# Electrode_Array_Hex_PCB.net
KiCad netlist of a schematic drawn in Altium Designer
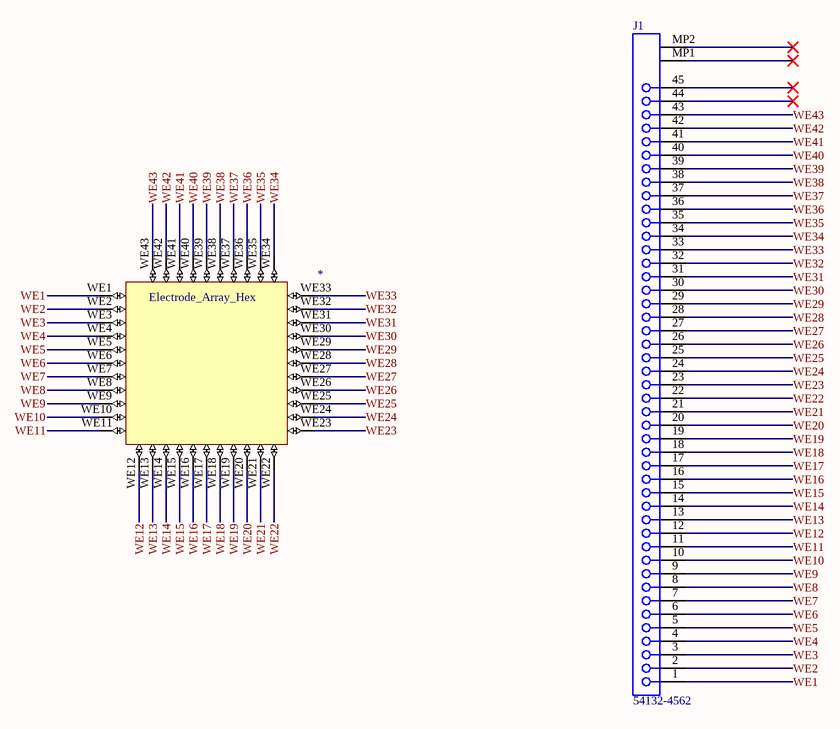
[diagram p0: Electrode_Array_Hex_PCB.SchDoc]

(export (version "E")
  (design (tool "Eeschema 10.0.6"))
  (components
    (comp (ref "*")
      (value "Electrode_Array_Hex")
      (footprint "PCBComponent_1")
      (libsource (lib "Electrode_Array_PCB_Hex") (part "Electrode_Array_Hex"))
    )
    (comp (ref "J1")
      (value "54132-4562")
      (footprint "MOLX-54132-4562")
      (fields (field (name "MANUFACTURER") "Molex"))
      (libsource (lib "Altium Content Vault") (part "MOLX-54132-4562"))
    )
  )
  (nets
    (net (code "1") (name "/WE1") (class "Default")
      (node (ref "*") (pin "WE1") (pintype "bidirectional"))
      (node (ref "J1") (pin "1") (pinfunction "1_1") (pintype "passive"))
    )
    (net (code "2") (name "/WE2") (class "Default")
      (node (ref "*") (pin "WE2") (pintype "bidirectional"))
      (node (ref "J1") (pin "2") (pinfunction "2_2") (pintype "passive"))
    )
    (net (code "3") (name "/WE3") (class "Default")
      (node (ref "*") (pin "WE3") (pintype "bidirectional"))
      (node (ref "J1") (pin "3") (pinfunction "3_3") (pintype "passive"))
    )
    (net (code "4") (name "/WE4") (class "Default")
      (node (ref "*") (pin "WE4") (pintype "bidirectional"))
      (node (ref "J1") (pin "4") (pinfunction "4_4") (pintype "passive"))
    )
    (net (code "5") (name "/WE5") (class "Default")
      (node (ref "*") (pin "WE5") (pintype "bidirectional"))
      (node (ref "J1") (pin "5") (pinfunction "5_5") (pintype "passive"))
    )
    (net (code "6") (name "/WE6") (class "Default")
      (node (ref "*") (pin "WE6") (pintype "bidirectional"))
      (node (ref "J1") (pin "6") (pinfunction "6_6") (pintype "passive"))
    )
    (net (code "7") (name "/WE7") (class "Default")
      (node (ref "*") (pin "WE7") (pintype "bidirectional"))
      (node (ref "J1") (pin "7") (pinfunction "7_7") (pintype "passive"))
    )
    (net (code "8") (name "/WE8") (class "Default")
      (node (ref "*") (pin "WE8") (pintype "bidirectional"))
      (node (ref "J1") (pin "8") (pinfunction "8_8") (pintype "passive"))
    )
    (net (code "9") (name "/WE9") (class "Default")
      (node (ref "*") (pin "WE9") (pintype "bidirectional"))
      (node (ref "J1") (pin "9") (pinfunction "9_9") (pintype "passive"))
    )
    (net (code "10") (name "/WE10") (class "Default")
      (node (ref "*") (pin "WE10") (pintype "bidirectional"))
      (node (ref "J1") (pin "10") (pinfunction "10_10") (pintype "passive"))
    )
    (net (code "11") (name "/WE11") (class "Default")
      (node (ref "*") (pin "WE11") (pintype "bidirectional"))
      (node (ref "J1") (pin "11") (pinfunction "11_11") (pintype "passive"))
    )
    (net (code "12") (name "/WE12") (class "Default")
      (node (ref "*") (pin "WE12") (pintype "bidirectional"))
      (node (ref "J1") (pin "12") (pinfunction "12_12") (pintype "passive"))
    )
    (net (code "13") (name "/WE13") (class "Default")
      (node (ref "*") (pin "WE13") (pintype "bidirectional"))
      (node (ref "J1") (pin "13") (pinfunction "13_13") (pintype "passive"))
    )
    (net (code "14") (name "/WE14") (class "Default")
      (node (ref "*") (pin "WE14") (pintype "bidirectional"))
      (node (ref "J1") (pin "14") (pinfunction "14_14") (pintype "passive"))
    )
    (net (code "15") (name "/WE15") (class "Default")
      (node (ref "*") (pin "WE15") (pintype "bidirectional"))
      (node (ref "J1") (pin "15") (pinfunction "15_15") (pintype "passive"))
    )
    (net (code "16") (name "/WE16") (class "Default")
      (node (ref "*") (pin "WE16") (pintype "bidirectional"))
      (node (ref "J1") (pin "16") (pinfunction "16_16") (pintype "passive"))
    )
    (net (code "17") (name "/WE17") (class "Default")
      (node (ref "*") (pin "WE17") (pintype "bidirectional"))
      (node (ref "J1") (pin "17") (pinfunction "17_17") (pintype "passive"))
    )
    (net (code "18") (name "/WE18") (class "Default")
      (node (ref "*") (pin "WE18") (pintype "bidirectional"))
      (node (ref "J1") (pin "18") (pinfunction "18_18") (pintype "passive"))
    )
    (net (code "19") (name "/WE19") (class "Default")
      (node (ref "*") (pin "WE19") (pintype "bidirectional"))
      (node (ref "J1") (pin "19") (pinfunction "19_19") (pintype "passive"))
    )
    (net (code "20") (name "/WE20") (class "Default")
      (node (ref "*") (pin "WE20") (pintype "bidirectional"))
      (node (ref "J1") (pin "20") (pinfunction "20_20") (pintype "passive"))
    )
    (net (code "21") (name "/WE21") (class "Default")
      (node (ref "*") (pin "WE21") (pintype "bidirectional"))
      (node (ref "J1") (pin "21") (pinfunction "21_21") (pintype "passive"))
    )
    (net (code "22") (name "/WE22") (class "Default")
      (node (ref "*") (pin "WE22") (pintype "bidirectional"))
      (node (ref "J1") (pin "22") (pinfunction "22_22") (pintype "passive"))
    )
    (net (code "23") (name "/WE23") (class "Default")
      (node (ref "*") (pin "WE23") (pintype "bidirectional"))
      (node (ref "J1") (pin "23") (pinfunction "23_23") (pintype "passive"))
    )
    (net (code "24") (name "/WE24") (class "Default")
      (node (ref "*") (pin "WE24") (pintype "bidirectional"))
      (node (ref "J1") (pin "24") (pinfunction "24_24") (pintype "passive"))
    )
    (net (code "25") (name "/WE25") (class "Default")
      (node (ref "*") (pin "WE25") (pintype "bidirectional"))
      (node (ref "J1") (pin "25") (pinfunction "25_25") (pintype "passive"))
    )
    (net (code "26") (name "/WE26") (class "Default")
      (node (ref "*") (pin "WE26") (pintype "bidirectional"))
      (node (ref "J1") (pin "26") (pinfunction "26_26") (pintype "passive"))
    )
    (net (code "27") (name "/WE27") (class "Default")
      (node (ref "*") (pin "WE27") (pintype "bidirectional"))
      (node (ref "J1") (pin "27") (pinfunction "27_27") (pintype "passive"))
    )
    (net (code "28") (name "/WE28") (class "Default")
      (node (ref "*") (pin "WE28") (pintype "bidirectional"))
      (node (ref "J1") (pin "28") (pinfunction "28_28") (pintype "passive"))
    )
    (net (code "29") (name "/WE29") (class "Default")
      (node (ref "*") (pin "WE29") (pintype "bidirectional"))
      (node (ref "J1") (pin "29") (pinfunction "29_29") (pintype "passive"))
    )
    (net (code "30") (name "/WE30") (class "Default")
      (node (ref "*") (pin "WE30") (pintype "bidirectional"))
      (node (ref "J1") (pin "30") (pinfunction "30_30") (pintype "passive"))
    )
    (net (code "31") (name "/WE31") (class "Default")
      (node (ref "*") (pin "WE31") (pintype "bidirectional"))
      (node (ref "J1") (pin "31") (pinfunction "31_31") (pintype "passive"))
    )
    (net (code "32") (name "/WE32") (class "Default")
      (node (ref "*") (pin "WE32") (pintype "bidirectional"))
      (node (ref "J1") (pin "32") (pinfunction "32_32") (pintype "passive"))
    )
    (net (code "33") (name "/WE33") (class "Default")
      (node (ref "*") (pin "WE33") (pintype "bidirectional"))
      (node (ref "J1") (pin "33") (pinfunction "33_33") (pintype "passive"))
    )
    (net (code "34") (name "/WE34") (class "Default")
      (node (ref "*") (pin "WE34") (pintype "bidirectional"))
      (node (ref "J1") (pin "34") (pinfunction "34_34") (pintype "passive"))
    )
    (net (code "35") (name "/WE35") (class "Default")
      (node (ref "*") (pin "WE35") (pintype "bidirectional"))
      (node (ref "J1") (pin "35") (pinfunction "35_35") (pintype "passive"))
    )
    (net (code "36") (name "/WE36") (class "Default")
      (node (ref "*") (pin "WE36") (pintype "bidirectional"))
      (node (ref "J1") (pin "36") (pinfunction "36_36") (pintype "passive"))
    )
    (net (code "37") (name "/WE37") (class "Default")
      (node (ref "*") (pin "WE37") (pintype "bidirectional"))
      (node (ref "J1") (pin "37") (pinfunction "37_37") (pintype "passive"))
    )
    (net (code "38") (name "/WE38") (class "Default")
      (node (ref "*") (pin "WE38") (pintype "bidirectional"))
      (node (ref "J1") (pin "38") (pinfunction "38_38") (pintype "passive"))
    )
    (net (code "39") (name "/WE39") (class "Default")
      (node (ref "*") (pin "WE39") (pintype "bidirectional"))
      (node (ref "J1") (pin "39") (pinfunction "39_39") (pintype "passive"))
    )
    (net (code "40") (name "/WE40") (class "Default")
      (node (ref "*") (pin "WE40") (pintype "bidirectional"))
      (node (ref "J1") (pin "40") (pinfunction "40_40") (pintype "passive"))
    )
    (net (code "41") (name "/WE41") (class "Default")
      (node (ref "*") (pin "WE41") (pintype "bidirectional"))
      (node (ref "J1") (pin "41") (pinfunction "41_41") (pintype "passive"))
    )
    (net (code "42") (name "/WE42") (class "Default")
      (node (ref "*") (pin "WE42") (pintype "bidirectional"))
      (node (ref "J1") (pin "42") (pinfunction "42_42") (pintype "passive"))
    )
    (net (code "43") (name "/WE43") (class "Default")
      (node (ref "*") (pin "WE43") (pintype "bidirectional"))
      (node (ref "J1") (pin "43") (pinfunction "43_43") (pintype "passive"))
    )
    (net (code "44") (name "unconnected-(J1-Pad44)") (class "Default")
      (node (ref "J1") (pin "44") (pinfunction "44_44") (pintype "passive+no_connect"))
    )
    (net (code "45") (name "unconnected-(J1-Pad45)") (class "Default")
      (node (ref "J1") (pin "45") (pinfunction "45_45") (pintype "passive+no_connect"))
    )
    (net (code "46") (name "unconnected-(J1-PadMP1)") (class "Default")
      (node (ref "J1") (pin "MP1") (pinfunction "MP1_MP1") (pintype "passive+no_connect"))
    )
    (net (code "47") (name "unconnected-(J1-PadMP2)") (class "Default")
      (node (ref "J1") (pin "MP2") (pinfunction "MP2_MP2") (pintype "passive+no_connect"))
    )
  )
)
